# CAN_Tranceiver.net
KiCad netlist of a schematic drawn in Altium Designer
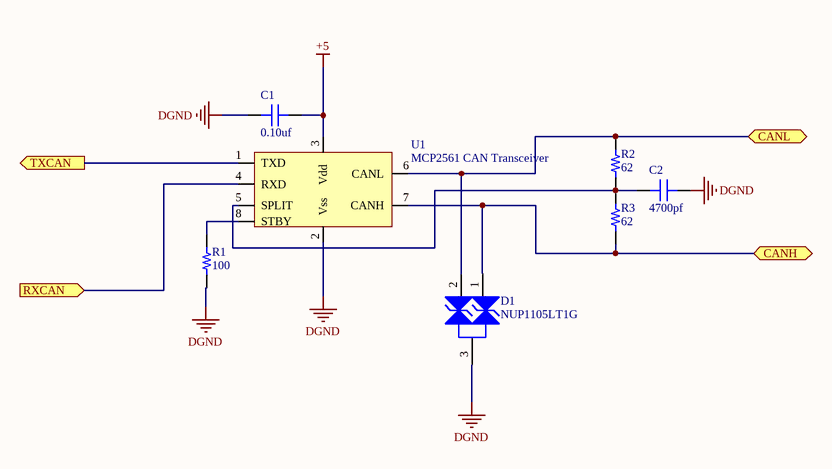
[diagram p0: CAN_Tranceiver.SchDoc]

(export (version "E")
  (design (tool "Eeschema 10.0.6"))
  (components
    (comp (ref "C1")
      (value "0.10uf")
      (footprint "CAP 0603/1608")
      (fields
        (field (name "Comment") "Capacitor MLCC 0.10uf 50V CAP 0603/1608")
        (field (name "CREATED_BY") "Nick Mah")
      )
      (libsource (lib "Altium-Lib") (part "Capacitor"))
    )
    (comp (ref "C2")
      (value "4700pf")
      (footprint "CAP 0603/1608")
      (fields
        (field (name "Comment") "Capacitor MLCC 4700pf 50V CAP 0603/1608")
        (field (name "CREATED_BY") "Nick Mah")
      )
      (libsource (lib "Altium-Lib") (part "Capacitor"))
    )
    (comp (ref "D1")
      (value "NUP1105LT1G")
      (footprint "SOT-23 (TO-236)")
      (description "ESD Protection Diode")
      (fields (field (name "POWER") "350W"))
      (libsource (lib "Altium-Lib") (part "NUP1105LT1G"))
    )
    (comp (ref "R1")
      (value "100")
      (footprint "RES 0603/1608")
      (fields
        (field (name "TOLERANCE") "10%")
        (field (name "POWER") "1/10W")
        (field (name "Comment") "Resistor 100 0603 1/10W 10%")
        (field (name "CREATED_BY") "Nick Mah")
      )
      (libsource (lib "Altium-Lib") (part "Resistor"))
    )
    (comp (ref "R2")
      (value "62")
      (footprint "RES 0603/1608")
      (fields
        (field (name "TOLERANCE") "5%")
        (field (name "POWER") "1/10W")
        (field (name "Comment") "Resistor 62 0603 1/10W 5%")
        (field (name "CREATED_BY") "Nick Mah")
      )
      (libsource (lib "Altium-Lib") (part "Resistor"))
    )
    (comp (ref "R3")
      (value "62")
      (footprint "RES 0603/1608")
      (fields
        (field (name "TOLERANCE") "5%")
        (field (name "POWER") "1/10W")
        (field (name "Comment") "Resistor 62 0603 1/10W 5%")
        (field (name "CREATED_BY") "Nick Mah")
      )
      (libsource (lib "Altium-Lib") (part "Resistor"))
    )
    (comp (ref "U1")
      (value "MCP2561 CAN Transceiver")
      (footprint "SOIC-8")
      (fields (field (name "MFRPARTNO") "MCP2561") (field (name "CREATED_BY") "Angel Delgado"))
      (libsource (lib "Altium-Lib") (part "MCP2561 CAN Transceiver"))
    )
  )
  (nets
    (net (code "1") (name "+5") (class "Default")
      (node (ref "C1") (pin "2") (pinfunction "2_2") (pintype "passive"))
      (node (ref "U1") (pin "3") (pinfunction "Vdd_3") (pintype "power_in"))
    )
    (net (code "2") (name "/CANH") (class "Default")
      (node (ref "D1") (pin "1") (pinfunction "K_1") (pintype "passive"))
      (node (ref "R3") (pin "2") (pinfunction "2_2") (pintype "passive"))
      (node (ref "U1") (pin "7") (pinfunction "CANH_7") (pintype "passive"))
    )
    (net (code "3") (name "/CANL") (class "Default")
      (node (ref "D1") (pin "2") (pinfunction "K_2") (pintype "passive"))
      (node (ref "R2") (pin "1") (pinfunction "1_1") (pintype "passive"))
      (node (ref "U1") (pin "6") (pinfunction "CANL_6") (pintype "passive"))
    )
    (net (code "4") (name "/RXCAN") (class "Default")
      (node (ref "U1") (pin "4") (pinfunction "RXD_4") (pintype "passive"))
    )
    (net (code "5") (name "/TXCAN") (class "Default")
      (node (ref "U1") (pin "1") (pinfunction "TXD_1") (pintype "passive"))
    )
    (net (code "6") (name "DGND") (class "Default")
      (node (ref "C1") (pin "1") (pinfunction "1_1") (pintype "passive"))
      (node (ref "C2") (pin "1") (pinfunction "1_1") (pintype "passive"))
      (node (ref "D1") (pin "3") (pinfunction "K_3") (pintype "passive"))
      (node (ref "R1") (pin "1") (pinfunction "1_1") (pintype "passive"))
      (node (ref "U1") (pin "2") (pinfunction "Vss_2") (pintype "power_in"))
    )
    (net (code "7") (name "Net-(U1-SPLIT)") (class "Default")
      (node (ref "C2") (pin "2") (pinfunction "2_2") (pintype "passive"))
      (node (ref "R2") (pin "2") (pinfunction "2_2") (pintype "passive"))
      (node (ref "R3") (pin "1") (pinfunction "1_1") (pintype "passive"))
      (node (ref "U1") (pin "5") (pinfunction "SPLIT_5") (pintype "passive"))
    )
    (net (code "8") (name "Net-(U1-STBY)") (class "Default")
      (node (ref "R1") (pin "2") (pinfunction "2_2") (pintype "passive"))
      (node (ref "U1") (pin "8") (pinfunction "STBY_8") (pintype "passive"))
    )
  )
)
